# New2.net
KiCad netlist of a schematic drawn in EAGLE
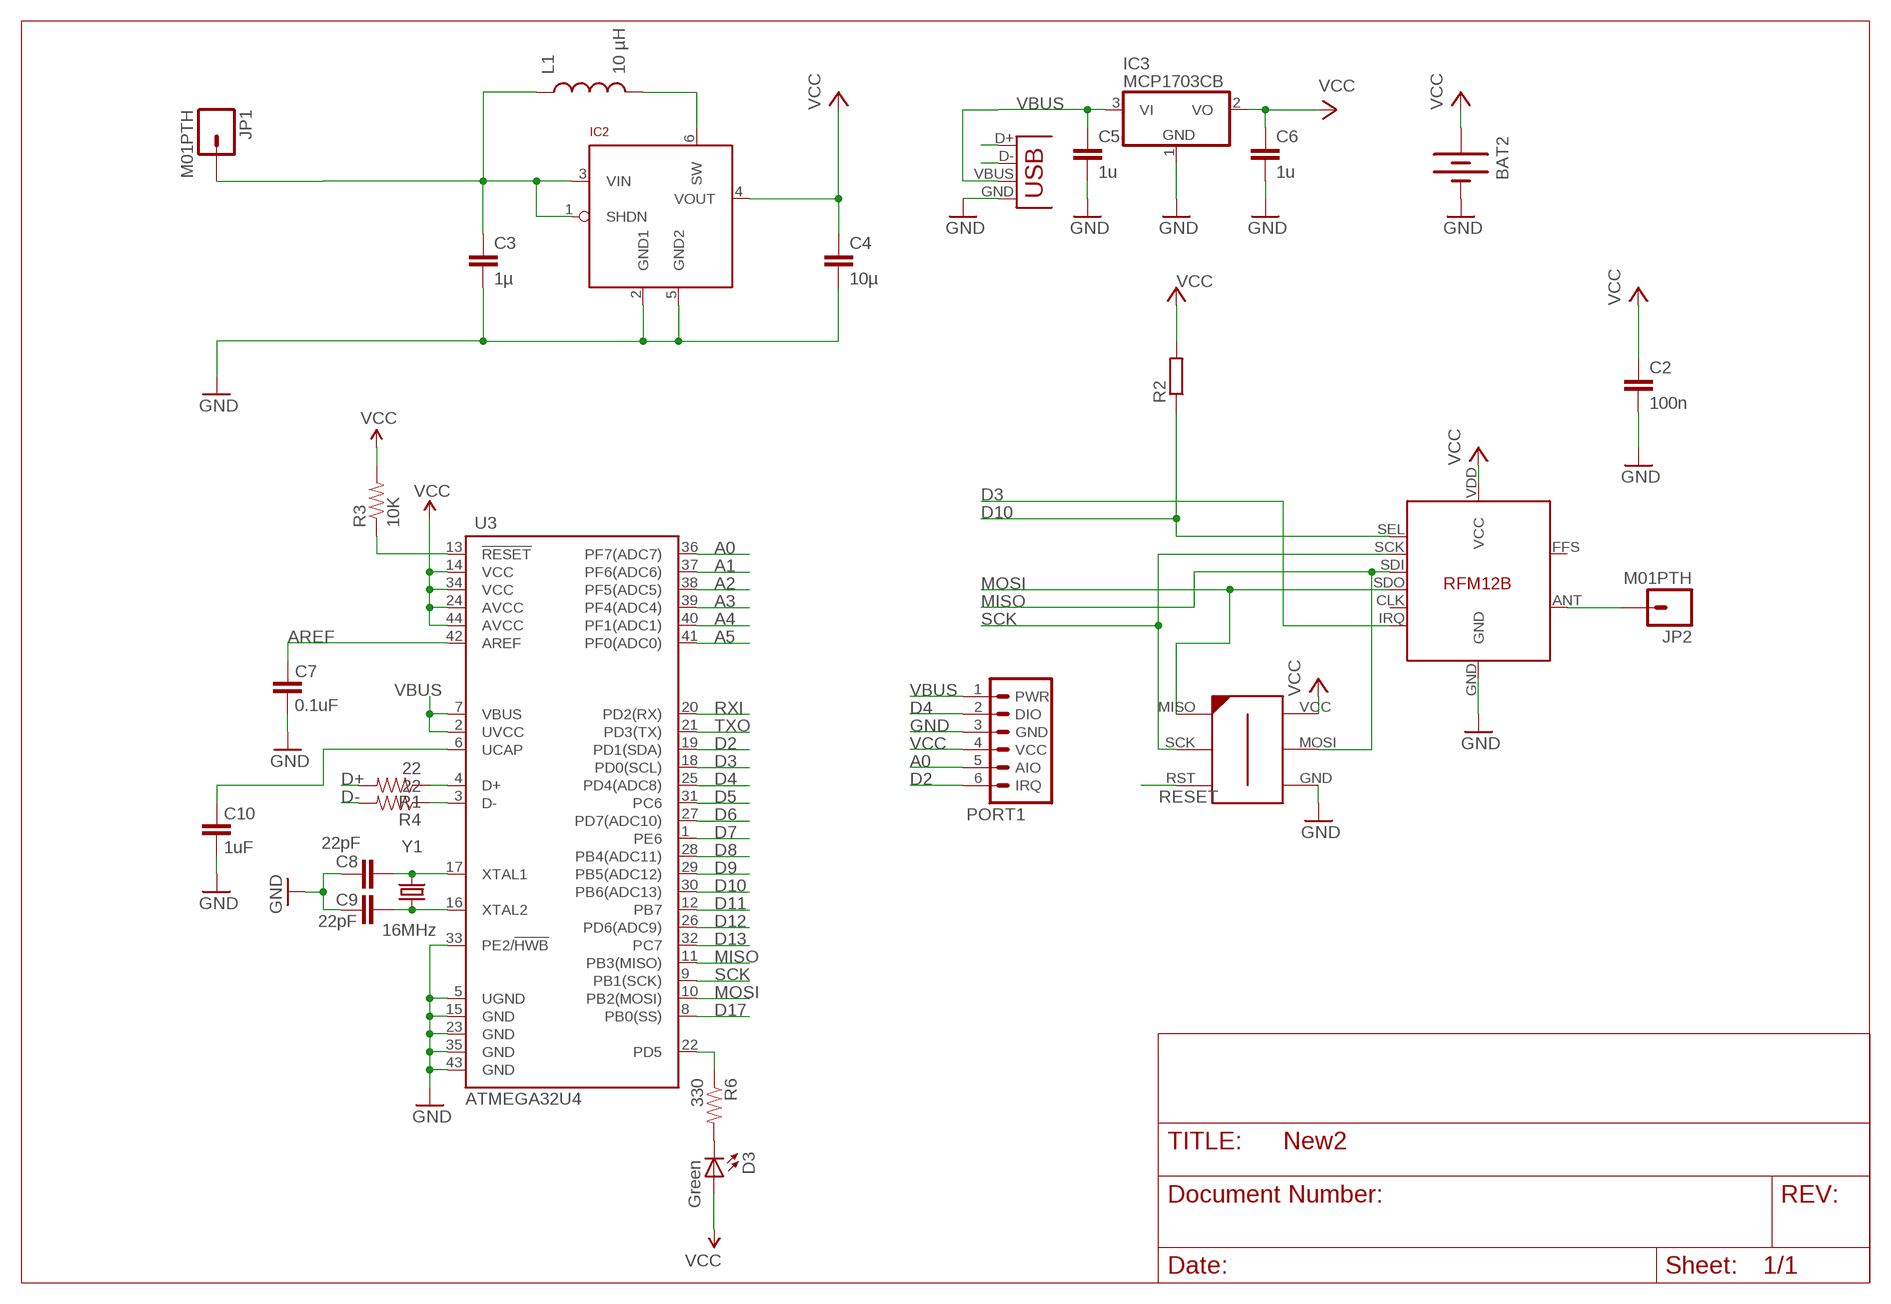
[diagram p0: schematic, sheet 1]

(export (version "E")
  (design (tool "Eeschema 10.0.6"))
  (components
    (comp (ref "BAT2")
      (value "BATTERY20PTH")
      (footprint "eagle-import:BATTCOM_20MM_PTH")
      (libsource (lib "eagle-import") (part "BATTERY20PTH"))
    )
    (comp (ref "C2")
      (value "100n")
      (footprint "eagle-import:C0603K")
      (libsource (lib "eagle-import") (part "C-EUC0603K"))
    )
    (comp (ref "C3")
      (value "1µ")
      (footprint "eagle-import:0603-CAP")
      (libsource (lib "eagle-import") (part "CAP0603-CAP"))
    )
    (comp (ref "C4")
      (value "10µ")
      (footprint "eagle-import:0805")
      (libsource (lib "eagle-import") (part "CAP0805"))
    )
    (comp (ref "C5")
      (value "1u")
      (footprint "eagle-import:C0603K")
      (libsource (lib "eagle-import") (part "C-EUC0603K"))
    )
    (comp (ref "C6")
      (value "1u")
      (footprint "eagle-import:C0603K")
      (libsource (lib "eagle-import") (part "C-EUC0603K"))
    )
    (comp (ref "C7")
      (value "0.1uF")
      (footprint "eagle-import:0402-CAP")
      (libsource (lib "eagle-import") (part "CAP0402-CAP"))
    )
    (comp (ref "C8")
      (value "22pF")
      (footprint "eagle-import:0402-CAP")
      (libsource (lib "eagle-import") (part "CAP0402-CAP"))
    )
    (comp (ref "C9")
      (value "22pF")
      (footprint "eagle-import:0402-CAP")
      (libsource (lib "eagle-import") (part "CAP0402-CAP"))
    )
    (comp (ref "C10")
      (value "1uF")
      (footprint "eagle-import:0402-CAP")
      (libsource (lib "eagle-import") (part "CAP0402-CAP"))
    )
    (comp (ref "D3")
      (value "Green")
      (footprint "eagle-import:LED-0603")
      (libsource (lib "eagle-import") (part "LED0603"))
    )
    (comp (ref "IC2")
      (value "LTC3525")
      (footprint "eagle-import:SC70")
      (libsource (lib "eagle-import") (part "LTC3525"))
    )
    (comp (ref "IC3")
      (value "MCP1703CB")
      (footprint "eagle-import:SOT23")
      (libsource (lib "eagle-import") (part "MCP1703CB"))
    )
    (comp (ref "JP1")
      (value "M01PTH")
      (footprint "eagle-import:1X01")
      (libsource (lib "eagle-import") (part "M01PTH"))
    )
    (comp (ref "JP2")
      (value "M01PTH")
      (footprint "eagle-import:1X01")
      (libsource (lib "eagle-import") (part "M01PTH"))
    )
    (comp (ref "L1")
      (value "10 µH")
      (footprint "eagle-import:1210")
      (libsource (lib "eagle-import") (part "INDUCTOR1210"))
    )
    (comp (ref "PORT1")
      (value "JEEPORT-FEMALE")
      (footprint "eagle-import:1X06_FEMALE_LOCK.010")
      (libsource (lib "eagle-import") (part "JEEPORT-FEMALE"))
    )
    (comp (ref "R1")
      (value "22")
      (footprint "eagle-import:0402-RES")
      (libsource (lib "eagle-import") (part "RESISTOR0402-RES"))
    )
    (comp (ref "R2")
      (value "R-EU_R0402")
      (footprint "eagle-import:R0402")
      (libsource (lib "eagle-import") (part "R-EU_R0402"))
    )
    (comp (ref "R3")
      (value "10K")
      (footprint "eagle-import:0402-RES")
      (libsource (lib "eagle-import") (part "RESISTOR0402-RES"))
    )
    (comp (ref "R4")
      (value "22")
      (footprint "eagle-import:0402-RES")
      (libsource (lib "eagle-import") (part "RESISTOR0402-RES"))
    )
    (comp (ref "R6")
      (value "330")
      (footprint "eagle-import:0402-RES")
      (libsource (lib "eagle-import") (part "RESISTOR0402-RES"))
    )
    (comp (ref "U$1")
      (value "RFM12B")
      (footprint "eagle-import:RFM12B")
      (libsource (lib "eagle-import") (part "RFM12B"))
    )
    (comp (ref "U$2")
      (value "AVR-ISP-6-EDGE")
      (footprint "eagle-import:6PAD_ISP")
      (libsource (lib "eagle-import") (part "AVR-ISP-6-EDGE"))
    )
    (comp (ref "U3")
      (value "ATMEGA32U4")
      (footprint "eagle-import:QFN-44-NOPAD")
      (libsource (lib "eagle-import") (part "ATMEGA32U4QFN2"))
    )
    (comp (ref "X1")
      (value "USB-MICROB")
      (footprint "eagle-import:USB-MICROB")
      (libsource (lib "eagle-import") (part "USB-MICROB"))
    )
    (comp (ref "Y1")
      (value "16MHz")
      (footprint "eagle-import:CRYSTAL-SMD-5X3")
      (libsource (lib "eagle-import") (part "CRYSTAL5X3"))
    )
  )
  (nets
    (net (code "1") (name "/A0") (class "Default")
      (node (ref "PORT1") (pin "5") (pinfunction "AIO_5") (pintype "bidirectional"))
      (node (ref "U3") (pin "36") (pinfunction "PF7(ADC7)_36") (pintype "bidirectional"))
    )
    (net (code "2") (name "/A1") (class "Default")
      (node (ref "U3") (pin "37") (pinfunction "PF6(ADC6)_37") (pintype "bidirectional"))
    )
    (net (code "3") (name "/A2") (class "Default")
      (node (ref "U3") (pin "38") (pinfunction "PF5(ADC5)_38") (pintype "bidirectional"))
    )
    (net (code "4") (name "/A3") (class "Default")
      (node (ref "U3") (pin "39") (pinfunction "PF4(ADC4)_39") (pintype "bidirectional"))
    )
    (net (code "5") (name "/A4") (class "Default")
      (node (ref "U3") (pin "40") (pinfunction "PF1(ADC1)_40") (pintype "bidirectional"))
    )
    (net (code "6") (name "/A5") (class "Default")
      (node (ref "U3") (pin "41") (pinfunction "PF0(ADC0)_41") (pintype "bidirectional"))
    )
    (net (code "7") (name "/AREF") (class "Default")
      (node (ref "C7") (pin "2") (pinfunction "2_2") (pintype "passive"))
      (node (ref "U3") (pin "42") (pinfunction "AREF_42") (pintype "bidirectional"))
    )
    (net (code "8") (name "/D+") (class "Default")
      (node (ref "R1") (pin "2") (pinfunction "2_2") (pintype "passive"))
      (node (ref "X1") (pin "D+") (pinfunction "D+_D+") (pintype "bidirectional"))
    )
    (net (code "9") (name "/D-") (class "Default")
      (node (ref "R4") (pin "2") (pinfunction "2_2") (pintype "passive"))
      (node (ref "X1") (pin "D-") (pinfunction "D-_D-") (pintype "bidirectional"))
    )
    (net (code "10") (name "/D2") (class "Default")
      (node (ref "PORT1") (pin "6") (pinfunction "IRQ_6") (pintype "bidirectional"))
      (node (ref "U3") (pin "19") (pinfunction "PD1(SDA)_19") (pintype "bidirectional"))
    )
    (net (code "11") (name "/D3") (class "Default")
      (node (ref "U$1") (pin "IRQ") (pinfunction "IRQ_IRQ") (pintype "open_collector"))
      (node (ref "U3") (pin "18") (pinfunction "PD0(SCL)_18") (pintype "bidirectional"))
    )
    (net (code "12") (name "/D4") (class "Default")
      (node (ref "PORT1") (pin "2") (pinfunction "DIO_2") (pintype "bidirectional"))
      (node (ref "U3") (pin "25") (pinfunction "PD4(ADC8)_25") (pintype "bidirectional"))
    )
    (net (code "13") (name "/D5") (class "Default")
      (node (ref "U3") (pin "31") (pinfunction "PC6_31") (pintype "bidirectional"))
    )
    (net (code "14") (name "/D6") (class "Default")
      (node (ref "U3") (pin "27") (pinfunction "PD7(ADC10)_27") (pintype "bidirectional"))
    )
    (net (code "15") (name "/D7") (class "Default")
      (node (ref "U3") (pin "1") (pinfunction "PE6_1") (pintype "bidirectional"))
    )
    (net (code "16") (name "/D8") (class "Default")
      (node (ref "U3") (pin "28") (pinfunction "PB4(ADC11)_28") (pintype "bidirectional"))
    )
    (net (code "17") (name "/D9") (class "Default")
      (node (ref "U3") (pin "29") (pinfunction "PB5(ADC12)_29") (pintype "bidirectional"))
    )
    (net (code "18") (name "/D10") (class "Default")
      (node (ref "R2") (pin "1") (pinfunction "1_1") (pintype "passive"))
      (node (ref "U$1") (pin "SEL") (pinfunction "SEL_SEL") (pintype "input"))
      (node (ref "U3") (pin "30") (pinfunction "PB6(ADC13)_30") (pintype "bidirectional"))
    )
    (net (code "19") (name "/D11") (class "Default")
      (node (ref "U3") (pin "12") (pinfunction "PB7_12") (pintype "bidirectional"))
    )
    (net (code "20") (name "/D12") (class "Default")
      (node (ref "U3") (pin "26") (pinfunction "PD6(ADC9)_26") (pintype "bidirectional"))
    )
    (net (code "21") (name "/D13") (class "Default")
      (node (ref "U3") (pin "32") (pinfunction "PC7_32") (pintype "bidirectional"))
    )
    (net (code "22") (name "/D17") (class "Default")
      (node (ref "U3") (pin "8") (pinfunction "PB0(SS)_8") (pintype "bidirectional"))
    )
    (net (code "23") (name "/MISO") (class "Default")
      (node (ref "U$1") (pin "SDI") (pinfunction "SDI_SDI") (pintype "input"))
      (node (ref "U$2") (pin "MOSI") (pinfunction "P$5_MOSI") (pintype "bidirectional"))
      (node (ref "U3") (pin "11") (pinfunction "PB3(MISO)_11") (pintype "bidirectional"))
    )
    (net (code "24") (name "/MOSI") (class "Default")
      (node (ref "U$1") (pin "SDO") (pinfunction "SDO_SDO") (pintype "output"))
      (node (ref "U$2") (pin "MISO") (pinfunction "P$1_MISO") (pintype "bidirectional"))
      (node (ref "U3") (pin "10") (pinfunction "PB2(MOSI)_10") (pintype "bidirectional"))
    )
    (net (code "25") (name "/RESET") (class "Default")
      (node (ref "R3") (pin "1") (pinfunction "1_1") (pintype "passive"))
      (node (ref "U$2") (pin "RST") (pinfunction "P$3_RST") (pintype "bidirectional"))
      (node (ref "U3") (pin "13") (pinfunction "~{RESET}_13") (pintype "bidirectional"))
    )
    (net (code "26") (name "/RXI") (class "Default")
      (node (ref "U3") (pin "20") (pinfunction "PD2(RX)_20") (pintype "bidirectional"))
    )
    (net (code "27") (name "/SCK") (class "Default")
      (node (ref "U$1") (pin "SCK") (pinfunction "SCK_SCK") (pintype "input"))
      (node (ref "U$2") (pin "SCK") (pinfunction "P$2_SCK") (pintype "bidirectional"))
      (node (ref "U3") (pin "9") (pinfunction "PB1(SCK)_9") (pintype "bidirectional"))
    )
    (net (code "28") (name "/TXO") (class "Default")
      (node (ref "U3") (pin "21") (pinfunction "PD3(TX)_21") (pintype "bidirectional"))
    )
    (net (code "29") (name "/VBUS") (class "Default")
      (node (ref "C5") (pin "1") (pinfunction "1_1") (pintype "passive"))
      (node (ref "IC3") (pin "3") (pinfunction "VI_3") (pintype "input"))
      (node (ref "PORT1") (pin "1") (pinfunction "PWR_1") (pintype "power_in"))
      (node (ref "U3") (pin "2") (pinfunction "UVCC_2") (pintype "bidirectional"))
      (node (ref "U3") (pin "7") (pinfunction "VBUS_7") (pintype "bidirectional"))
      (node (ref "X1") (pin "VBUS") (pinfunction "VBUS_VBUS") (pintype "bidirectional"))
    )
    (net (code "30") (name "GND") (class "Default")
      (node (ref "BAT2") (pin "2") (pinfunction "-_2") (pintype "power_in"))
      (node (ref "C10") (pin "1") (pinfunction "1_1") (pintype "passive"))
      (node (ref "C2") (pin "2") (pinfunction "2_2") (pintype "passive"))
      (node (ref "C3") (pin "2") (pinfunction "2_2") (pintype "passive"))
      (node (ref "C4") (pin "2") (pinfunction "2_2") (pintype "passive"))
      (node (ref "C5") (pin "2") (pinfunction "2_2") (pintype "passive"))
      (node (ref "C6") (pin "2") (pinfunction "2_2") (pintype "passive"))
      (node (ref "C7") (pin "1") (pinfunction "1_1") (pintype "passive"))
      (node (ref "C8") (pin "2") (pinfunction "2_2") (pintype "passive"))
      (node (ref "C9") (pin "2") (pinfunction "2_2") (pintype "passive"))
      (node (ref "IC2") (pin "2") (pinfunction "GND1_2") (pintype "power_in"))
      (node (ref "IC2") (pin "5") (pinfunction "GND2_5") (pintype "power_in"))
      (node (ref "IC3") (pin "1") (pinfunction "GND_1") (pintype "passive"))
      (node (ref "PORT1") (pin "3") (pinfunction "GND_3") (pintype "power_in"))
      (node (ref "U$1") (pin "GND") (pinfunction "GND_GND") (pintype "power_in"))
      (node (ref "U$2") (pin "GND") (pinfunction "P$4_GND") (pintype "bidirectional"))
      (node (ref "U3") (pin "15") (pinfunction "GND_15") (pintype "bidirectional"))
      (node (ref "U3") (pin "23") (pinfunction "GND_23") (pintype "bidirectional"))
      (node (ref "U3") (pin "33") (pinfunction "PE2/~{HWB}_33") (pintype "bidirectional"))
      (node (ref "U3") (pin "35") (pinfunction "GND_35") (pintype "bidirectional"))
      (node (ref "U3") (pin "43") (pinfunction "GND_43") (pintype "bidirectional"))
      (node (ref "U3") (pin "5") (pinfunction "UGND_5") (pintype "bidirectional"))
      (node (ref "X1") (pin "GND") (pinfunction "GND_GND") (pintype "bidirectional"))
    )
    (net (code "31") (name "Net-(D3-PadC)") (class "Default")
      (node (ref "D3") (pin "C") (pinfunction "C_C") (pintype "passive"))
      (node (ref "R6") (pin "2") (pinfunction "2_2") (pintype "passive"))
    )
    (net (code "32") (name "Net-(IC2-SHDN)") (class "Default")
      (node (ref "C3") (pin "1") (pinfunction "1_1") (pintype "passive"))
      (node (ref "IC2") (pin "1") (pinfunction "SHDN_1") (pintype "input"))
      (node (ref "IC2") (pin "3") (pinfunction "VIN_3") (pintype "tri_state"))
      (node (ref "JP1") (pin "1") (pinfunction "1_1") (pintype "passive"))
      (node (ref "L1") (pin "1") (pinfunction "1_1") (pintype "passive"))
    )
    (net (code "33") (name "Net-(IC2-SW)") (class "Default")
      (node (ref "IC2") (pin "6") (pinfunction "SW_6") (pintype "power_in"))
      (node (ref "L1") (pin "2") (pinfunction "2_2") (pintype "passive"))
    )
    (net (code "34") (name "Net-(JP2-Pad1)") (class "Default")
      (node (ref "JP2") (pin "1") (pinfunction "1_1") (pintype "passive"))
      (node (ref "U$1") (pin "ANT") (pinfunction "ANT_ANT") (pintype "passive"))
    )
    (net (code "35") (name "Net-(U3-D+)") (class "Default")
      (node (ref "R1") (pin "1") (pinfunction "1_1") (pintype "passive"))
      (node (ref "U3") (pin "4") (pinfunction "D+_4") (pintype "bidirectional"))
    )
    (net (code "36") (name "Net-(U3-D-)") (class "Default")
      (node (ref "R4") (pin "1") (pinfunction "1_1") (pintype "passive"))
      (node (ref "U3") (pin "3") (pinfunction "D-_3") (pintype "bidirectional"))
    )
    (net (code "37") (name "Net-(U3-PD5)") (class "Default")
      (node (ref "R6") (pin "1") (pinfunction "1_1") (pintype "passive"))
      (node (ref "U3") (pin "22") (pinfunction "PD5_22") (pintype "bidirectional"))
    )
    (net (code "38") (name "Net-(U3-UCAP)") (class "Default")
      (node (ref "C10") (pin "2") (pinfunction "2_2") (pintype "passive"))
      (node (ref "U3") (pin "6") (pinfunction "UCAP_6") (pintype "bidirectional"))
    )
    (net (code "39") (name "Net-(U3-XTAL1)") (class "Default")
      (node (ref "C8") (pin "1") (pinfunction "1_1") (pintype "passive"))
      (node (ref "U3") (pin "17") (pinfunction "XTAL1_17") (pintype "bidirectional"))
      (node (ref "Y1") (pin "3") (pinfunction "2_3") (pintype "passive"))
    )
    (net (code "40") (name "Net-(U3-XTAL2)") (class "Default")
      (node (ref "C9") (pin "1") (pinfunction "1_1") (pintype "passive"))
      (node (ref "U3") (pin "16") (pinfunction "XTAL2_16") (pintype "bidirectional"))
      (node (ref "Y1") (pin "1") (pinfunction "1_1") (pintype "passive"))
    )
    (net (code "41") (name "VCC") (class "Default")
      (node (ref "BAT2") (pin "1") (pinfunction "+_1") (pintype "power_in"))
      (node (ref "C2") (pin "1") (pinfunction "1_1") (pintype "passive"))
      (node (ref "C4") (pin "1") (pinfunction "1_1") (pintype "passive"))
      (node (ref "C6") (pin "1") (pinfunction "1_1") (pintype "passive"))
      (node (ref "D3") (pin "A") (pinfunction "A_A") (pintype "passive"))
      (node (ref "IC2") (pin "4") (pinfunction "VOUT_4") (pintype "power_in"))
      (node (ref "IC3") (pin "2") (pinfunction "VO_2") (pintype "passive"))
      (node (ref "PORT1") (pin "4") (pinfunction "VCC_4") (pintype "power_in"))
      (node (ref "R2") (pin "2") (pinfunction "2_2") (pintype "passive"))
      (node (ref "R3") (pin "2") (pinfunction "2_2") (pintype "passive"))
      (node (ref "U$1") (pin "VDD") (pinfunction "VCC_VDD") (pintype "power_in"))
      (node (ref "U$2") (pin "VCC") (pinfunction "P$6_VCC") (pintype "bidirectional"))
      (node (ref "U3") (pin "14") (pinfunction "VCC_14") (pintype "bidirectional"))
      (node (ref "U3") (pin "24") (pinfunction "AVCC_24") (pintype "bidirectional"))
      (node (ref "U3") (pin "34") (pinfunction "VCC_34") (pintype "bidirectional"))
      (node (ref "U3") (pin "44") (pinfunction "AVCC_44") (pintype "bidirectional"))
    )
    (net (code "42") (name "unconnected-(U$1-PadCLK)") (class "Default")
      (node (ref "U$1") (pin "CLK") (pinfunction "CLK_CLK") (pintype "output"))
    )
    (net (code "43") (name "unconnected-(U$1-PadFFS)") (class "Default")
      (node (ref "U$1") (pin "FFS") (pinfunction "FFS_FFS") (pintype "bidirectional"))
    )
  )
)
